# xkid_0_2.net
KiCad netlist of a schematic drawn in EAGLE
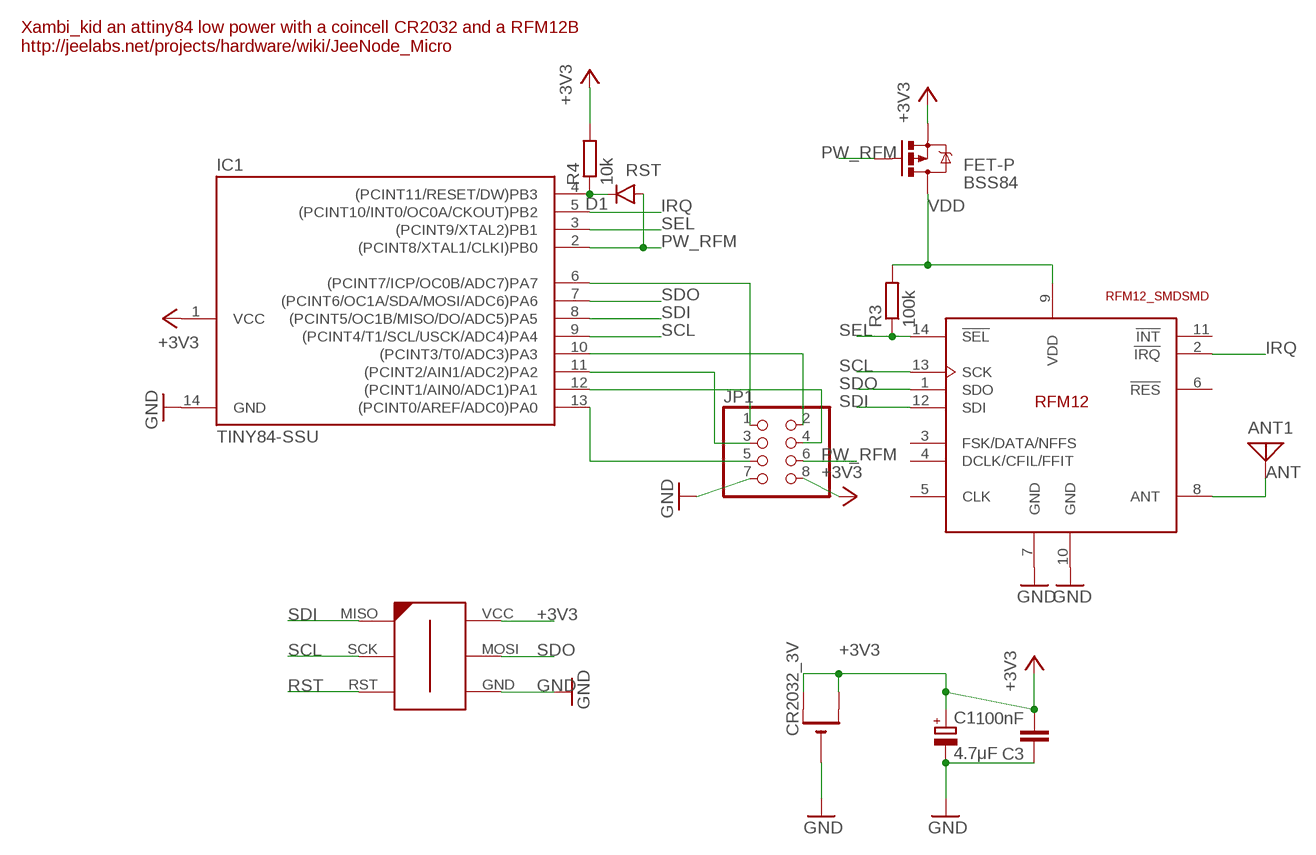
[diagram p0: schematic, sheet 1]

(export (version "E")
  (design (tool "Eeschema 10.0.6"))
  (components
    (comp (ref "ANT1")
      (value "ANTENNA")
      (footprint "eagle-import:PAD-01")
      (libsource (lib "eagle-import") (part "ANTENNA"))
    )
    (comp (ref "BSS84")
      (value "FET-P")
      (footprint "eagle-import:SOT23-3")
      (libsource (lib "eagle-import") (part "MOSFET-PCHANNEL"))
    )
    (comp (ref "C1")
      (value "4.7μF")
      (footprint "eagle-import:CT3216")
      (libsource (lib "eagle-import") (part "CPOL-EUCT3216"))
    )
    (comp (ref "C3")
      (value "100nF")
      (footprint "eagle-import:C0805K")
      (libsource (lib "eagle-import") (part "C-EUC0805K"))
    )
    (comp (ref "CR2032_3V")
      (value "CR2032THM")
      (footprint "eagle-import:CR2032-THRU")
      (libsource (lib "eagle-import") (part "CR2032THM"))
    )
    (comp (ref "D1")
      (value "DIODESOD")
      (footprint "eagle-import:SOD-323")
      (libsource (lib "eagle-import") (part "DIODESOD"))
    )
    (comp (ref "IC1")
      (value "TINY84-SSU")
      (footprint "eagle-import:SOIC14")
      (libsource (lib "eagle-import") (part "TINY24/44/84-SSU"))
    )
    (comp (ref "JP1")
      (value "PINHD-2X4_2.54")
      (footprint "eagle-import:2X04")
      (libsource (lib "eagle-import") (part "PINHD-2X4_2.54"))
    )
    (comp (ref "R3")
      (value "100k")
      (footprint "eagle-import:R0805")
      (libsource (lib "eagle-import") (part "R-EU_R0805"))
    )
    (comp (ref "R4")
      (value "10k")
      (footprint "eagle-import:R0805")
      (libsource (lib "eagle-import") (part "R-EU_R0805"))
    )
    (comp (ref "U$1")
      (value "RFM12_SMDSMD")
      (footprint "eagle-import:RFM12")
      (libsource (lib "eagle-import") (part "RFM12_SMDSMD"))
    )
    (comp (ref "U$2")
      (value "AVR-ISP-6-EDGE")
      (footprint "eagle-import:6PAD_ISP")
      (libsource (lib "eagle-import") (part "AVR-ISP-6-EDGE"))
    )
  )
  (nets
    (net (code "1") (name "+3V3") (class "Default")
      (node (ref "BSS84") (pin "2") (pinfunction "S_2") (pintype "passive"))
      (node (ref "C1") (pin "+") (pinfunction "+_+") (pintype "passive"))
      (node (ref "C3") (pin "2") (pinfunction "2_2") (pintype "passive"))
      (node (ref "CR2032_3V") (pin "+1") (pinfunction "+_+1") (pintype "passive"))
      (node (ref "CR2032_3V") (pin "+2") (pinfunction "+1_+2") (pintype "passive"))
      (node (ref "IC1") (pin "1") (pinfunction "VCC_1") (pintype "power_in"))
      (node (ref "JP1") (pin "8") (pinfunction "8_8") (pintype "passive"))
      (node (ref "R4") (pin "2") (pinfunction "2_2") (pintype "passive"))
      (node (ref "U$2") (pin "VCC") (pinfunction "P$6_VCC") (pintype "bidirectional"))
    )
    (net (code "2") (name "/ANT") (class "Default")
      (node (ref "ANT1") (pin "1") (pinfunction "1_1") (pintype "output"))
      (node (ref "U$1") (pin "8") (pinfunction "ANT_8") (pintype "bidirectional"))
    )
    (net (code "3") (name "/IRQ") (class "Default")
      (node (ref "IC1") (pin "5") (pinfunction "(PCINT10/INT0/OC0A/CKOUT)PB2_5") (pintype "bidirectional"))
      (node (ref "U$1") (pin "2") (pinfunction "~{IRQ}_2") (pintype "output"))
    )
    (net (code "4") (name "/PW_RFM") (class "Default")
      (node (ref "BSS84") (pin "1") (pinfunction "G_1") (pintype "passive"))
      (node (ref "D1") (pin "A") (pinfunction "A_A") (pintype "passive"))
      (node (ref "IC1") (pin "2") (pinfunction "(PCINT8/XTAL1/CLKI)PB0_2") (pintype "bidirectional"))
      (node (ref "JP1") (pin "6") (pinfunction "6_6") (pintype "passive"))
    )
    (net (code "5") (name "/RST") (class "Default")
      (node (ref "D1") (pin "C") (pinfunction "C_C") (pintype "passive"))
      (node (ref "IC1") (pin "4") (pinfunction "(PCINT11/RESET/DW)PB3_4") (pintype "bidirectional"))
      (node (ref "R4") (pin "1") (pinfunction "1_1") (pintype "passive"))
      (node (ref "U$2") (pin "RST") (pinfunction "P$3_RST") (pintype "bidirectional"))
    )
    (net (code "6") (name "/SCL") (class "Default")
      (node (ref "IC1") (pin "9") (pinfunction "(PCINT4/T1/SCL/USCK/ADC4)PA4_9") (pintype "bidirectional"))
      (node (ref "U$1") (pin "13") (pinfunction "SCK_13") (pintype "input"))
      (node (ref "U$2") (pin "SCK") (pinfunction "P$2_SCK") (pintype "bidirectional"))
    )
    (net (code "7") (name "/SDI") (class "Default")
      (node (ref "IC1") (pin "8") (pinfunction "(PCINT5/OC1B/MISO/DO/ADC5)PA5_8") (pintype "bidirectional"))
      (node (ref "U$1") (pin "12") (pinfunction "SDI_12") (pintype "input"))
      (node (ref "U$2") (pin "MISO") (pinfunction "P$1_MISO") (pintype "bidirectional"))
    )
    (net (code "8") (name "/SDO") (class "Default")
      (node (ref "IC1") (pin "7") (pinfunction "(PCINT6/OC1A/SDA/MOSI/ADC6)PA6_7") (pintype "bidirectional"))
      (node (ref "U$1") (pin "1") (pinfunction "SDO_1") (pintype "output"))
      (node (ref "U$2") (pin "MOSI") (pinfunction "P$5_MOSI") (pintype "bidirectional"))
    )
    (net (code "9") (name "/SEL") (class "Default")
      (node (ref "IC1") (pin "3") (pinfunction "(PCINT9/XTAL2)PB1_3") (pintype "bidirectional"))
      (node (ref "R3") (pin "1") (pinfunction "1_1") (pintype "passive"))
      (node (ref "U$1") (pin "14") (pinfunction "~{SEL}_14") (pintype "input"))
    )
    (net (code "10") (name "/VDD") (class "Default")
      (node (ref "BSS84") (pin "3") (pinfunction "D_3") (pintype "passive"))
      (node (ref "R3") (pin "2") (pinfunction "2_2") (pintype "passive"))
      (node (ref "U$1") (pin "9") (pinfunction "VDD_9") (pintype "power_in"))
    )
    (net (code "11") (name "GND") (class "Default")
      (node (ref "C1") (pin "-") (pinfunction "-_-") (pintype "passive"))
      (node (ref "C3") (pin "1") (pinfunction "1_1") (pintype "passive"))
      (node (ref "CR2032_3V") (pin "-") (pinfunction "-_-") (pintype "passive"))
      (node (ref "IC1") (pin "14") (pinfunction "GND_14") (pintype "power_in"))
      (node (ref "JP1") (pin "7") (pinfunction "7_7") (pintype "passive"))
      (node (ref "U$1") (pin "10") (pinfunction "GND_10") (pintype "passive"))
      (node (ref "U$1") (pin "7") (pinfunction "GND_7") (pintype "passive"))
      (node (ref "U$2") (pin "GND") (pinfunction "P$4_GND") (pintype "bidirectional"))
    )
    (net (code "12") (name "Net-(IC1-(PCINT0{slash}AREF{slash}ADC0)PA0)") (class "Default")
      (node (ref "IC1") (pin "13") (pinfunction "(PCINT0/AREF/ADC0)PA0_13") (pintype "bidirectional"))
      (node (ref "JP1") (pin "5") (pinfunction "5_5") (pintype "passive"))
    )
    (net (code "13") (name "Net-(IC1-(PCINT1{slash}AIN0{slash}ADC1)PA1)") (class "Default")
      (node (ref "IC1") (pin "12") (pinfunction "(PCINT1/AIN0/ADC1)PA1_12") (pintype "bidirectional"))
      (node (ref "JP1") (pin "4") (pinfunction "4_4") (pintype "passive"))
    )
    (net (code "14") (name "Net-(IC1-(PCINT2{slash}AIN1{slash}ADC2)PA2)") (class "Default")
      (node (ref "IC1") (pin "11") (pinfunction "(PCINT2/AIN1/ADC2)PA2_11") (pintype "bidirectional"))
      (node (ref "JP1") (pin "3") (pinfunction "3_3") (pintype "passive"))
    )
    (net (code "15") (name "Net-(IC1-(PCINT3{slash}T0{slash}ADC3)PA3)") (class "Default")
      (node (ref "IC1") (pin "10") (pinfunction "(PCINT3/T0/ADC3)PA3_10") (pintype "bidirectional"))
      (node (ref "JP1") (pin "2") (pinfunction "2_2") (pintype "passive"))
    )
    (net (code "16") (name "Net-(IC1-(PCINT7{slash}ICP{slash}OC0B{slash}ADC7)PA7)") (class "Default")
      (node (ref "IC1") (pin "6") (pinfunction "(PCINT7/ICP/OC0B/ADC7)PA7_6") (pintype "bidirectional"))
      (node (ref "JP1") (pin "1") (pinfunction "1_1") (pintype "passive"))
    )
    (net (code "17") (name "unconnected-(U$1-CLK-Pad5)") (class "Default")
      (node (ref "U$1") (pin "5") (pinfunction "CLK_5") (pintype "output"))
    )
    (net (code "18") (name "unconnected-(U$1-DCLK{slash}CFIL{slash}FFIT-Pad4)") (class "Default")
      (node (ref "U$1") (pin "4") (pinfunction "DCLK/CFIL/FFIT_4") (pintype "bidirectional"))
    )
    (net (code "19") (name "unconnected-(U$1-FSK{slash}DATA{slash}NFFS-Pad3)") (class "Default")
      (node (ref "U$1") (pin "3") (pinfunction "FSK/DATA/NFFS_3") (pintype "bidirectional"))
    )
    (net (code "20") (name "unconnected-(U$1-~{INT}-Pad11)") (class "Default")
      (node (ref "U$1") (pin "11") (pinfunction "~{INT}_11") (pintype "bidirectional"))
    )
    (net (code "21") (name "unconnected-(U$1-~{RES}-Pad6)") (class "Default")
      (node (ref "U$1") (pin "6") (pinfunction "~{RES}_6") (pintype "bidirectional"))
    )
  )
)
